# amc7135-20mm-dia-350mA-led-driver-mk-1_0.net
KiCad netlist of a schematic drawn in EAGLE
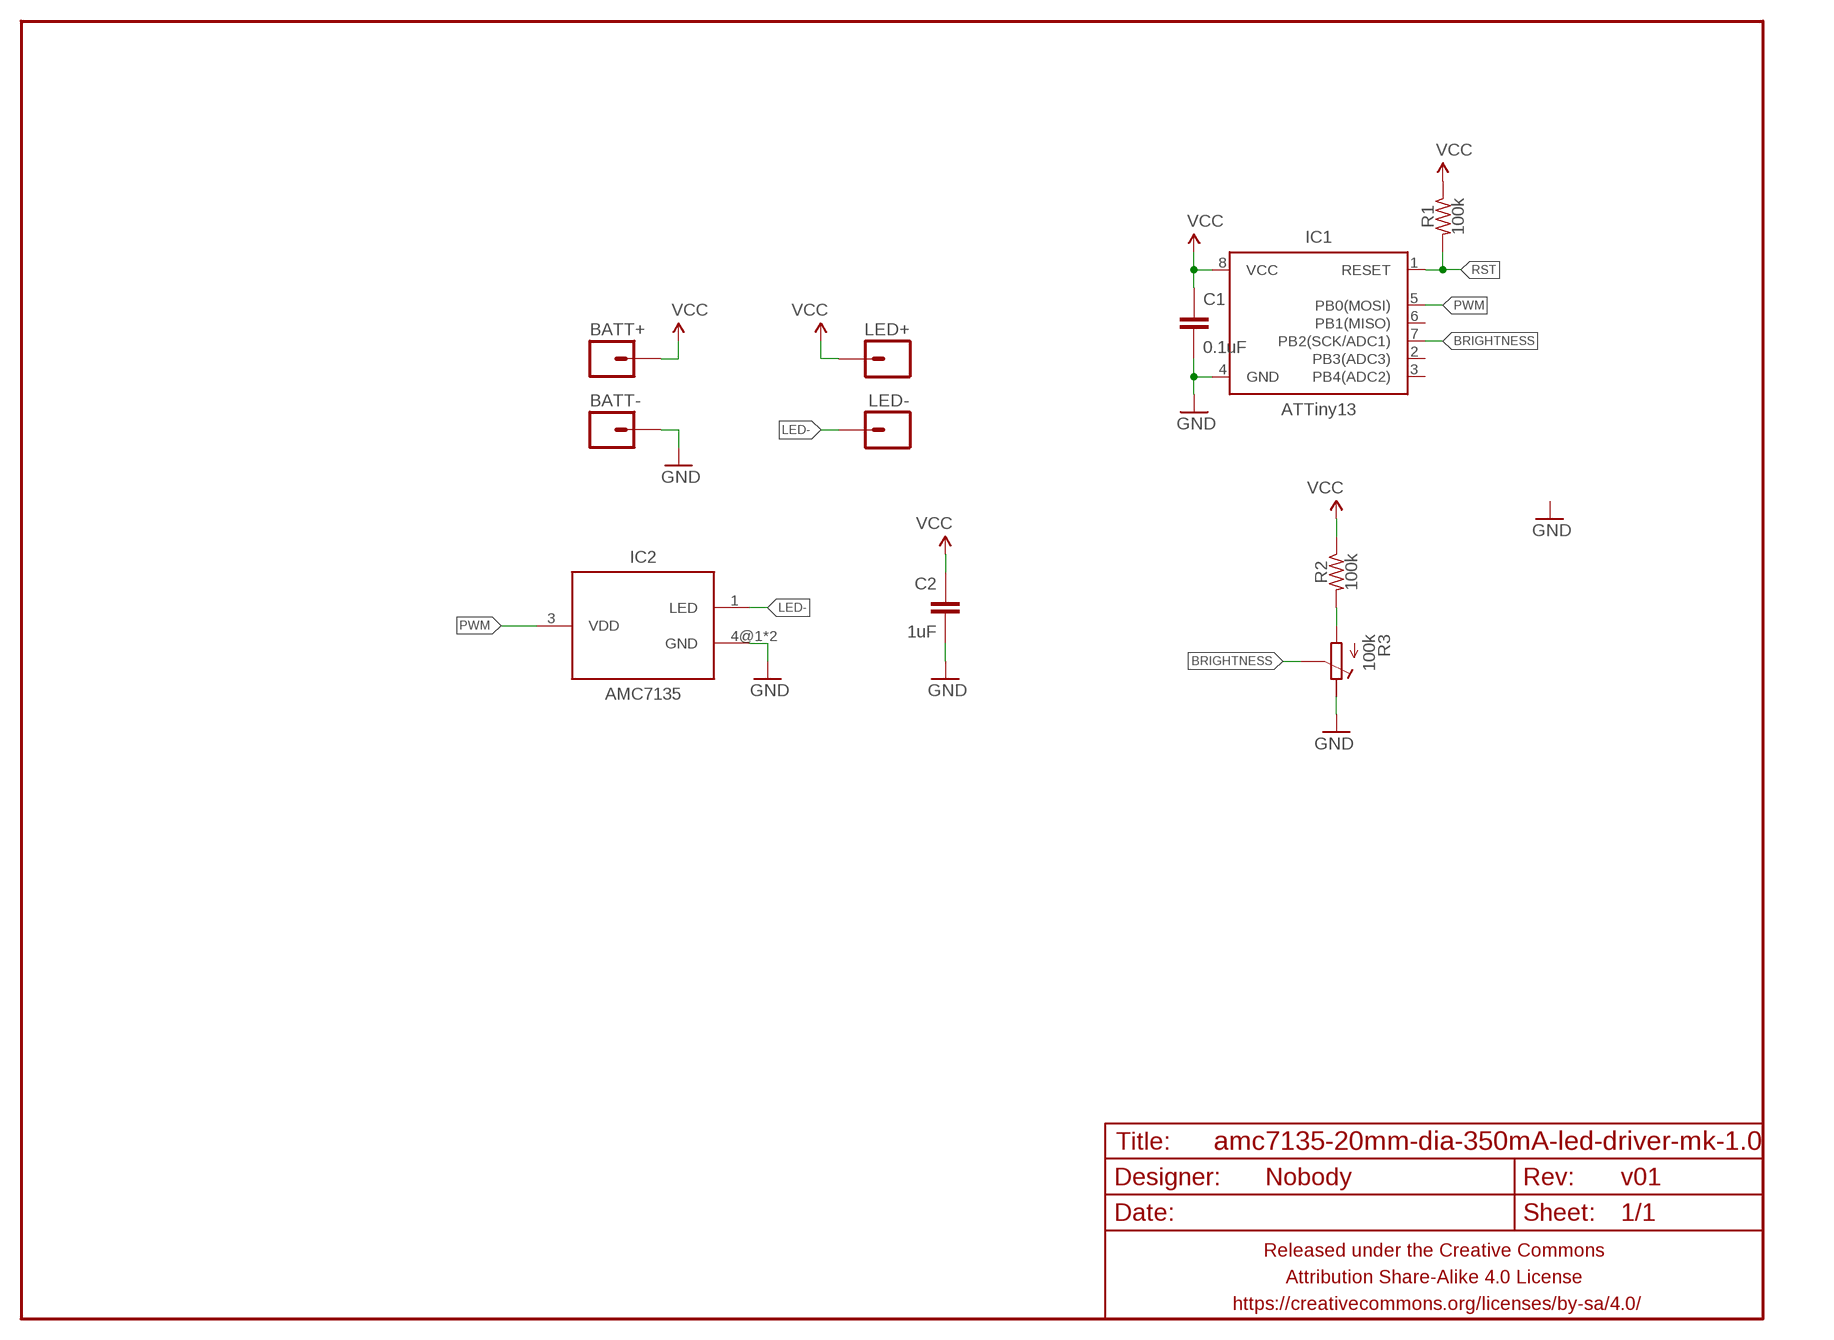
[diagram p0: schematic, sheet 1]

(export (version "E")
  (design (tool "Eeschema 10.0.6"))
  (components
    (comp (ref "BATT+")
      (value "M01NOT-A-VIA-NOPE")
      (footprint "eagle-import:1X01_NOSILK_NOSTOP")
      (libsource (lib "eagle-import") (part "M01NOT-A-VIA-NOPE"))
    )
    (comp (ref "BATT-")
      (value "M01NOT-A-VIA-NOPE")
      (footprint "eagle-import:1X01_NOSILK_NOSTOP")
      (libsource (lib "eagle-import") (part "M01NOT-A-VIA-NOPE"))
    )
    (comp (ref "C1")
      (value "0.1uF")
      (footprint "eagle-import:C0805")
      (libsource (lib "eagle-import") (part "CAPACITOR-CERAMICC0805"))
    )
    (comp (ref "C2")
      (value "1uF")
      (footprint "eagle-import:C1206")
      (libsource (lib "eagle-import") (part "CAPACITOR-CERAMICC1206"))
    )
    (comp (ref "FRAME1")
      (value "FRAME-LETTERNO_PACKAGE")
      (footprint "eagle-import:DUMMY")
      (fields (field (name "DESIGNER") "Nobody"))
      (libsource (lib "eagle-import") (part "FRAME-LETTERNO_PACKAGE"))
    )
    (comp (ref "IC1")
      (value "ATTiny13")
      (footprint "eagle-import:SO08")
      (libsource (lib "eagle-import") (part "ATTINY13SOIC"))
    )
    (comp (ref "IC2")
      (value "AMC7135")
      (footprint "eagle-import:SOT89-NOTHERM")
      (libsource (lib "eagle-import") (part "AMC7135SOT-89-NOTHERM"))
    )
    (comp (ref "LED+")
      (value "M01PTH-1.2MM")
      (footprint "eagle-import:1X01-1.2MM")
      (libsource (lib "eagle-import") (part "M01PTH-1.2MM"))
    )
    (comp (ref "LED-")
      (value "M01PTH-1.2MM-NS")
      (footprint "eagle-import:1X01-1.2MM-NS")
      (libsource (lib "eagle-import") (part "M01PTH-1.2MM-NS"))
    )
    (comp (ref "R1")
      (value "100k")
      (footprint "eagle-import:R0805")
      (libsource (lib "eagle-import") (part "RESISTORR0805"))
    )
    (comp (ref "R2")
      (value "100k")
      (footprint "eagle-import:R0805")
      (libsource (lib "eagle-import") (part "RESISTORR0805"))
    )
    (comp (ref "R3")
      (value "100k")
      (footprint "eagle-import:EVM3Y")
      (libsource (lib "eagle-import") (part "POTENTIOMETEREVM3Y"))
    )
  )
  (nets
    (net (code "1") (name "BRIGHTNESS") (class "Default")
      (node (ref "IC1") (pin "7") (pinfunction "PB2(SCK/ADC1)_7") (pintype "bidirectional"))
      (node (ref "R3") (pin "S") (pinfunction "S_S") (pintype "passive"))
    )
    (net (code "2") (name "GND") (class "Default")
      (node (ref "BATT-") (pin "P$1") (pinfunction "1_P$1") (pintype "passive"))
      (node (ref "C1") (pin "2") (pinfunction "2_2") (pintype "passive"))
      (node (ref "C2") (pin "2") (pinfunction "2_2") (pintype "passive"))
      (node (ref "IC1") (pin "4") (pinfunction "GND_4") (pintype "bidirectional"))
      (node (ref "IC2") (pin "4@1") (pinfunction "GND_4@1") (pintype "bidirectional"))
      (node (ref "IC2") (pin "4@2") (pinfunction "GND_4@2") (pintype "bidirectional"))
      (node (ref "R3") (pin "E") (pinfunction "E_E") (pintype "passive"))
    )
    (net (code "3") (name "LED-") (class "Default")
      (node (ref "IC2") (pin "1") (pinfunction "LED_1") (pintype "bidirectional"))
      (node (ref "LED-") (pin "P$1") (pinfunction "1_P$1") (pintype "passive"))
    )
    (net (code "4") (name "Net-(R2-Pad2)") (class "Default")
      (node (ref "R2") (pin "2") (pinfunction "2_2") (pintype "passive"))
      (node (ref "R3") (pin "A") (pinfunction "A_A") (pintype "passive"))
    )
    (net (code "5") (name "PWM") (class "Default")
      (node (ref "IC1") (pin "5") (pinfunction "PB0(MOSI)_5") (pintype "bidirectional"))
      (node (ref "IC2") (pin "3") (pinfunction "VDD_3") (pintype "bidirectional"))
    )
    (net (code "6") (name "RST") (class "Default")
      (node (ref "IC1") (pin "1") (pinfunction "RESET_1") (pintype "bidirectional"))
      (node (ref "R1") (pin "2") (pinfunction "2_2") (pintype "passive"))
    )
    (net (code "7") (name "VCC") (class "Default")
      (node (ref "BATT+") (pin "P$1") (pinfunction "1_P$1") (pintype "passive"))
      (node (ref "C1") (pin "1") (pinfunction "1_1") (pintype "passive"))
      (node (ref "C2") (pin "1") (pinfunction "1_1") (pintype "passive"))
      (node (ref "IC1") (pin "8") (pinfunction "VCC_8") (pintype "bidirectional"))
      (node (ref "LED+") (pin "P$1") (pinfunction "1_P$1") (pintype "passive"))
      (node (ref "R1") (pin "1") (pinfunction "1_1") (pintype "passive"))
      (node (ref "R2") (pin "1") (pinfunction "1_1") (pintype "passive"))
    )
    (net (code "8") (name "unconnected-(IC1-PB1(MISO)-Pad6)") (class "Default")
      (node (ref "IC1") (pin "6") (pinfunction "PB1(MISO)_6") (pintype "bidirectional"))
    )
    (net (code "9") (name "unconnected-(IC1-PB3(ADC3)-Pad2)") (class "Default")
      (node (ref "IC1") (pin "2") (pinfunction "PB3(ADC3)_2") (pintype "bidirectional"))
    )
    (net (code "10") (name "unconnected-(IC1-PB4(ADC2)-Pad3)") (class "Default")
      (node (ref "IC1") (pin "3") (pinfunction "PB4(ADC2)_3") (pintype "bidirectional"))
    )
  )
)
